# Grove_-_NunChuck_v1_0.net
KiCad netlist of a schematic drawn in EAGLE
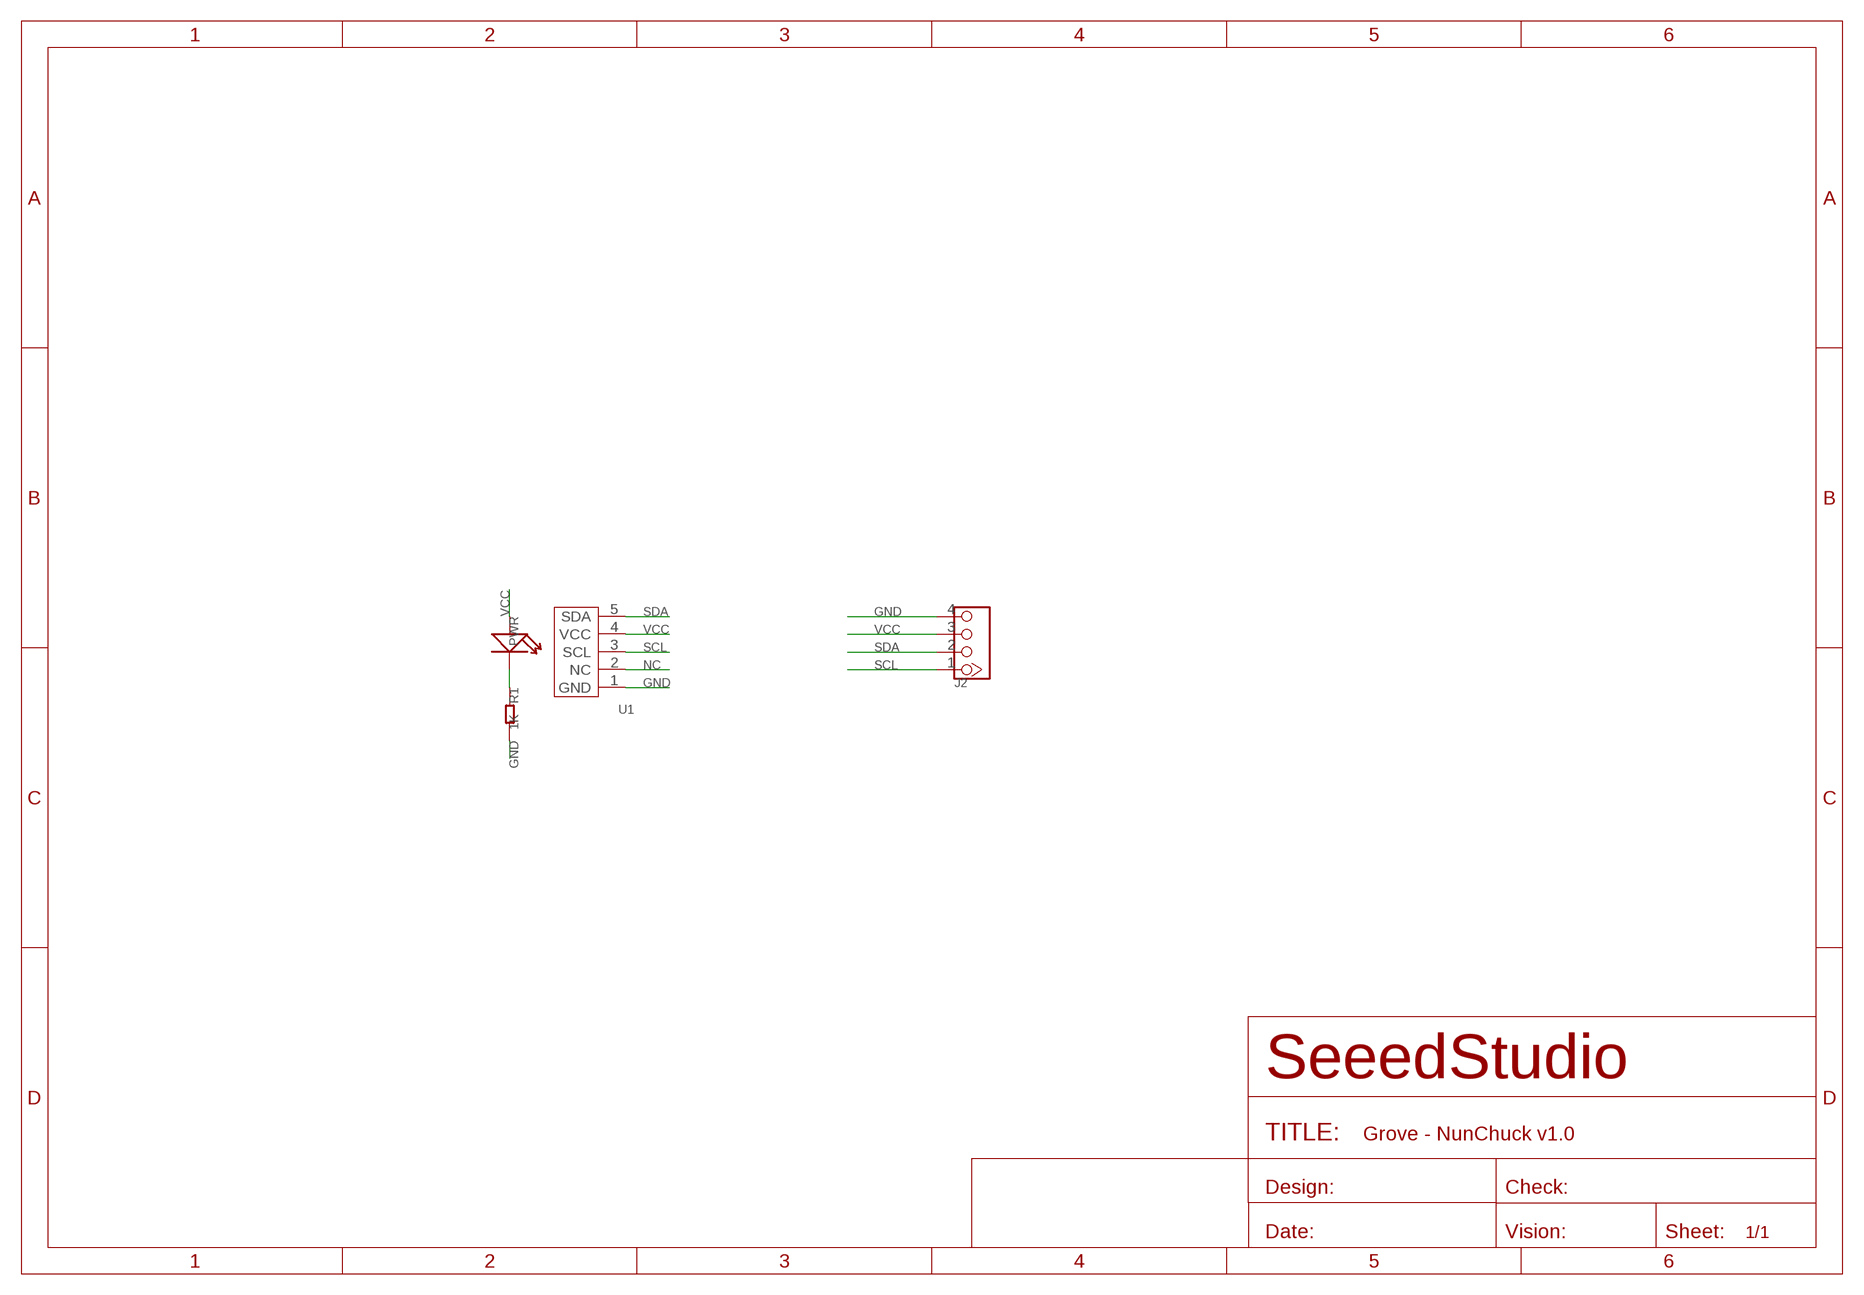
[diagram p0: schematic, sheet 1]

(export (version "E")
  (design (tool "Eeschema 10.0.6"))
  (components
    (comp (ref "J2")
      (value "TWIG-4P-2.0-2.0")
      (footprint "eagle-import:4P-2.0")
      (libsource (lib "eagle-import") (part "TWIG-4P-2.0-2.0"))
    )
    (comp (ref "PWR")
      (value "LED'0603'")
      (footprint "eagle-import:LED-0603")
      (libsource (lib "eagle-import") (part "LED'0603'"))
    )
    (comp (ref "R1")
      (value "1K")
      (footprint "eagle-import:R0603")
      (libsource (lib "eagle-import") (part "R-0603"))
    )
    (comp (ref "U1")
      (value "WIICHUCK")
      (footprint "eagle-import:WIICHUCK")
      (libsource (lib "eagle-import") (part "WIICHUCK"))
    )
  )
  (nets
    (net (code "1") (name "/GND") (class "Default")
      (node (ref "J2") (pin "4") (pinfunction "4_4") (pintype "bidirectional"))
      (node (ref "R1") (pin "2") (pinfunction "2_2") (pintype "passive"))
      (node (ref "U1") (pin "1") (pinfunction "GND_1") (pintype "bidirectional"))
    )
    (net (code "2") (name "/NC") (class "Default")
      (node (ref "U1") (pin "2") (pinfunction "NC_2") (pintype "bidirectional"))
    )
    (net (code "3") (name "/SCL") (class "Default")
      (node (ref "J2") (pin "1") (pinfunction "1_1") (pintype "bidirectional"))
      (node (ref "U1") (pin "3") (pinfunction "SCL_3") (pintype "bidirectional"))
    )
    (net (code "4") (name "/SDA") (class "Default")
      (node (ref "J2") (pin "2") (pinfunction "2_2") (pintype "bidirectional"))
      (node (ref "U1") (pin "5") (pinfunction "SDA_5") (pintype "bidirectional"))
    )
    (net (code "5") (name "/VCC") (class "Default")
      (node (ref "J2") (pin "3") (pinfunction "3_3") (pintype "bidirectional"))
      (node (ref "PWR") (pin "+") (pinfunction "+_+") (pintype "passive"))
      (node (ref "U1") (pin "4") (pinfunction "VCC_4") (pintype "bidirectional"))
    )
    (net (code "6") (name "Net-(PWR-Pad-)") (class "Default")
      (node (ref "PWR") (pin "-") (pinfunction "-_-") (pintype "passive"))
      (node (ref "R1") (pin "1") (pinfunction "1_1") (pintype "passive"))
    )
  )
)
